# NT_MCUModule.net
KiCad netlist of a schematic drawn in EAGLE
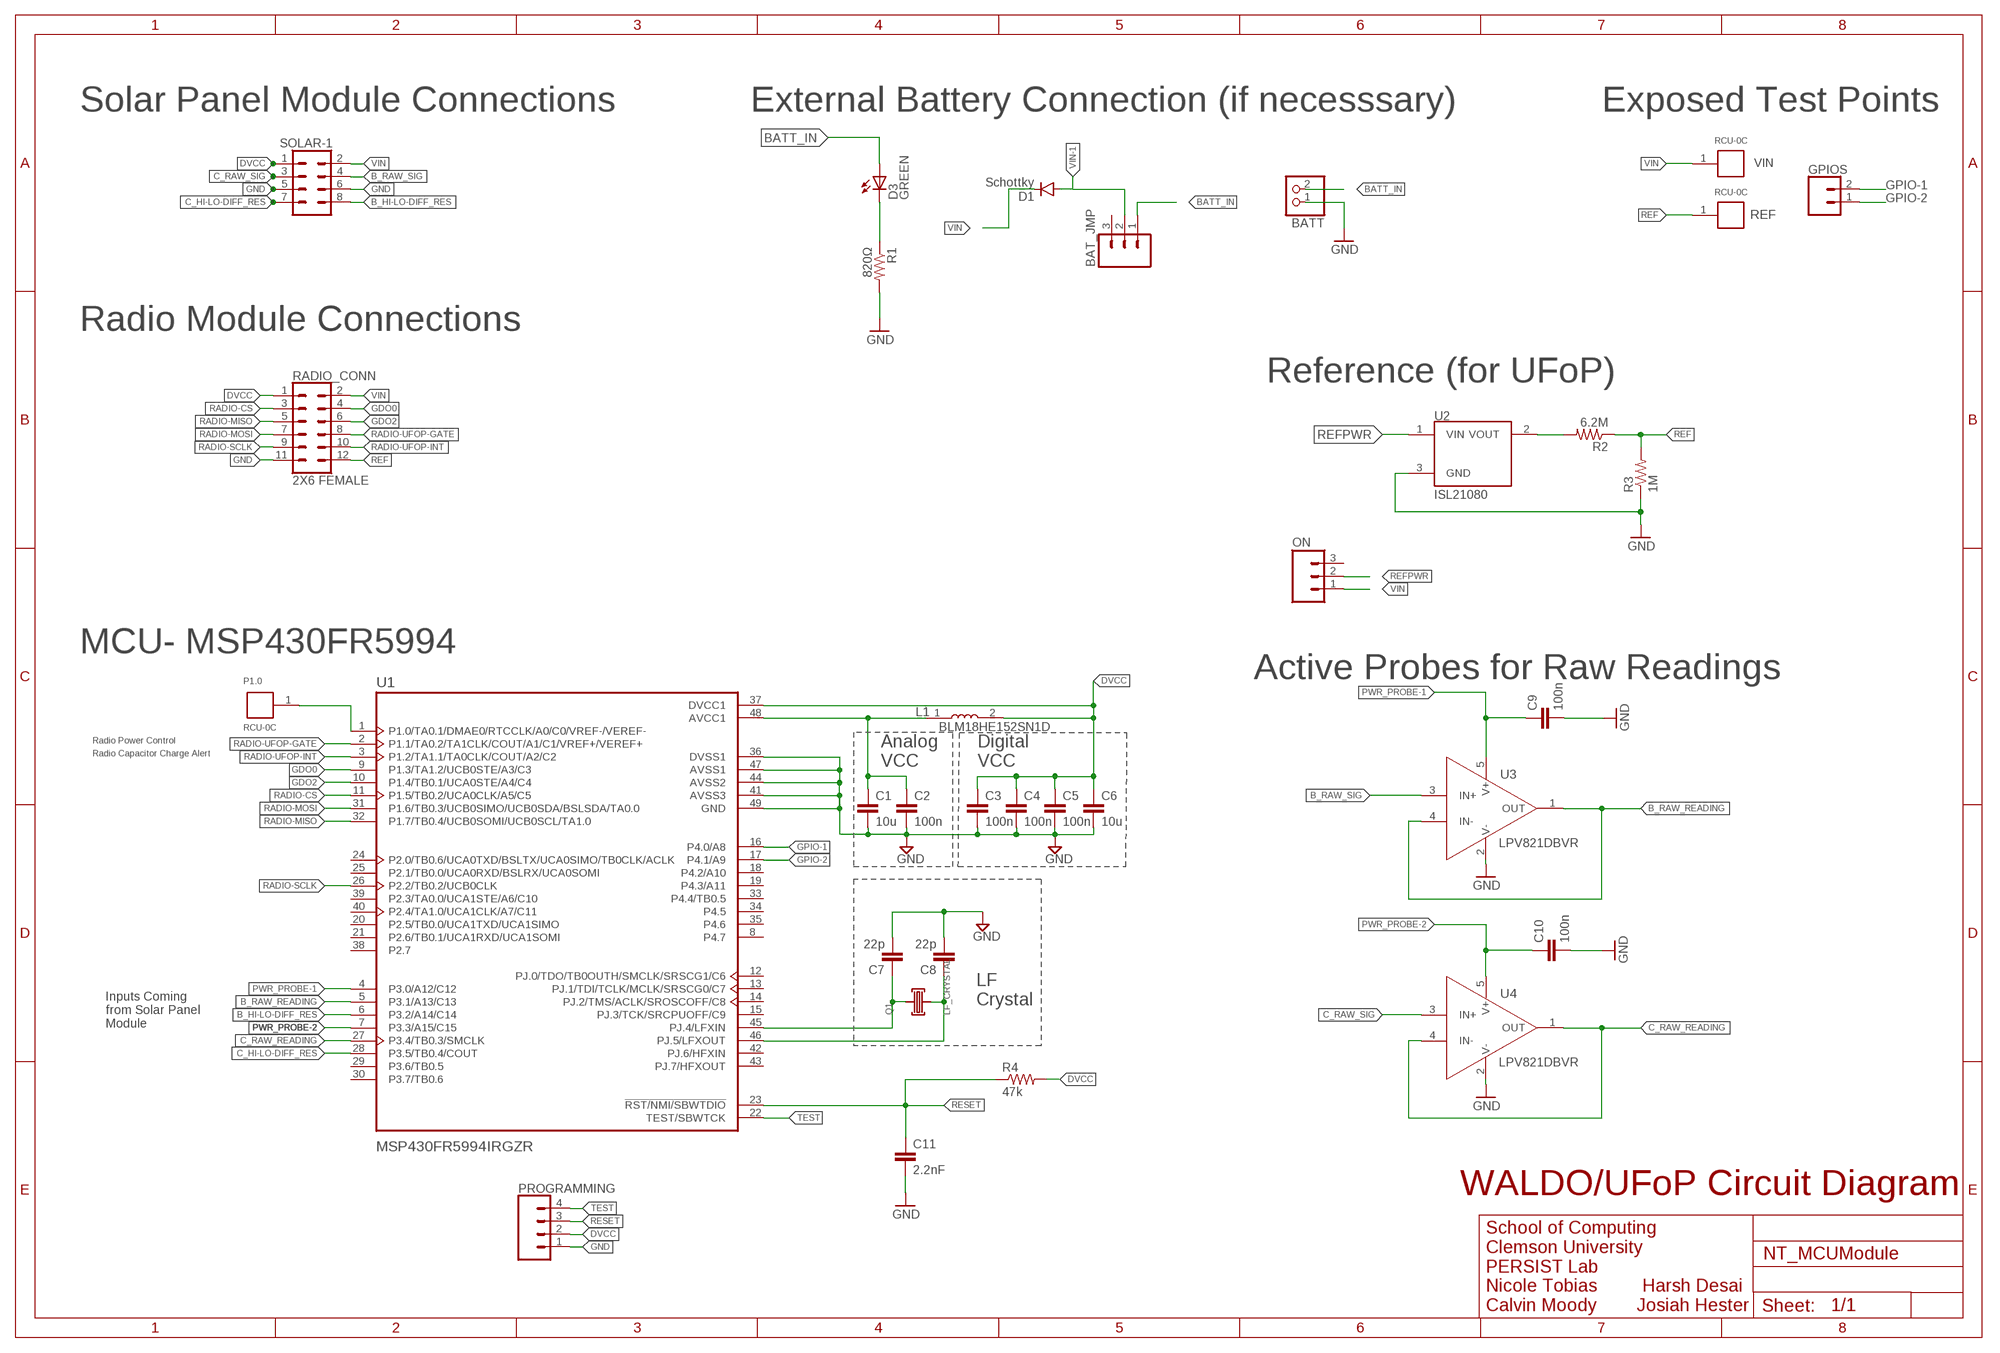
[diagram p0: schematic, sheet 1]

(export (version "E")
  (design (tool "Eeschema 10.0.6"))
  (components
    (comp (ref "BATT")
      (value "PINHD-1X2")
      (footprint "eagle-import:1X02")
      (libsource (lib "eagle-import") (part "PINHD-1X2"))
    )
    (comp (ref "BAT_JMP")
      (value "M03")
      (footprint "eagle-import:1X03-1.27MM")
      (libsource (lib "eagle-import") (part "M03"))
    )
    (comp (ref "C1")
      (value "10u")
      (footprint "eagle-import:C0603")
      (libsource (lib "eagle-import") (part "C-EUC0603"))
    )
    (comp (ref "C2")
      (value "100n")
      (footprint "eagle-import:C0603")
      (libsource (lib "eagle-import") (part "C-EUC0603"))
    )
    (comp (ref "C3")
      (value "100n")
      (footprint "eagle-import:C0603")
      (libsource (lib "eagle-import") (part "C-EUC0603"))
    )
    (comp (ref "C4")
      (value "100n")
      (footprint "eagle-import:C0603")
      (libsource (lib "eagle-import") (part "C-EUC0603"))
    )
    (comp (ref "C5")
      (value "100n")
      (footprint "eagle-import:C0603")
      (libsource (lib "eagle-import") (part "C-EUC0603"))
    )
    (comp (ref "C6")
      (value "10u")
      (footprint "eagle-import:C0603")
      (libsource (lib "eagle-import") (part "C-EUC0603"))
    )
    (comp (ref "C7")
      (value "22p")
      (footprint "eagle-import:C0603")
      (libsource (lib "eagle-import") (part "C-EUC0603"))
    )
    (comp (ref "C8")
      (value "22p")
      (footprint "eagle-import:C0603")
      (libsource (lib "eagle-import") (part "C-EUC0603"))
    )
    (comp (ref "C9")
      (value "100n")
      (footprint "eagle-import:C0603")
      (libsource (lib "eagle-import") (part "C-EUC0603"))
    )
    (comp (ref "C10")
      (value "100n")
      (footprint "eagle-import:C0603")
      (libsource (lib "eagle-import") (part "C-EUC0603"))
    )
    (comp (ref "C11")
      (value "2.2nF")
      (footprint "eagle-import:C0603")
      (libsource (lib "eagle-import") (part "C-EUC0603"))
    )
    (comp (ref "D1")
      (value "Schottky")
      (footprint "eagle-import:SOD523")
      (libsource (lib "eagle-import") (part "DIODESOD523"))
    )
    (comp (ref "D3")
      (value "GREEN")
      (footprint "eagle-import:CHIP-LED0805")
      (libsource (lib "eagle-import") (part "LEDCHIP-LED0805"))
    )
    (comp (ref "GPIOS")
      (value "CONN_02")
      (footprint "eagle-import:1X02")
      (libsource (lib "eagle-import") (part "CONN_02"))
    )
    (comp (ref "L1")
      (value "BLM18HE152SN1D")
      (footprint "eagle-import:INDC1608X95")
      (fields (field (name "DIGI-KEY_PART_NUMBER") "490-5216-1-ND") (field (name "MF") "Murata"))
      (libsource (lib "eagle-import") (part "BLM18HE152SN1D"))
    )
    (comp (ref "ON")
      (value "M03")
      (footprint "eagle-import:1X03-1.27MM")
      (libsource (lib "eagle-import") (part "M03"))
    )
    (comp (ref "P1.0")
      (value "RCU-0C")
      (footprint "eagle-import:TE_RCU-0C")
      (fields
        (field (name "COMMENT") "RCU-0C _1625854-3_")
        (field (name "MF") "TE Connectivity")
        (field (name "TOLERANCE") "0%")
      )
      (libsource (lib "eagle-import") (part "RCU-0C"))
    )
    (comp (ref "PROGRAMMING")
      (value "CONN_04")
      (footprint "eagle-import:1X04")
      (libsource (lib "eagle-import") (part "CONN_04"))
    )
    (comp (ref "Q1")
      (value "LF_CRYSTAL")
      (footprint "eagle-import:LF_CRYSTAL")
      (libsource (lib "eagle-import") (part "LF_CRYSTAL"))
    )
    (comp (ref "R1")
      (value "820Ω")
      (footprint "eagle-import:0603-RES")
      (libsource (lib "eagle-import") (part "RESISTOR0603"))
    )
    (comp (ref "R2")
      (value "6.2M")
      (footprint "eagle-import:0603-RES")
      (libsource (lib "eagle-import") (part "RESISTOR0603-RES"))
    )
    (comp (ref "R3")
      (value "1M")
      (footprint "eagle-import:0603-RES")
      (libsource (lib "eagle-import") (part "RESISTOR0603-RES"))
    )
    (comp (ref "R4")
      (value "47k")
      (footprint "eagle-import:0603-RES")
      (libsource (lib "eagle-import") (part "RESISTOR0603-RES"))
    )
    (comp (ref "RADIO_CONN")
      (value "2X6 FEMALE")
      (footprint "eagle-import:2X6")
      (libsource (lib "eagle-import") (part "CONN_06X2PTH_FEMALE"))
    )
    (comp (ref "REF")
      (value "RCU-0C")
      (footprint "eagle-import:TE_RCU-0C")
      (fields
        (field (name "COMMENT") "RCU-0C _1625854-3_")
        (field (name "MF") "TE Connectivity")
        (field (name "TOLERANCE") "0%")
      )
      (libsource (lib "eagle-import") (part "RCU-0C"))
    )
    (comp (ref "SOLAR-1")
      (value "CONN_04X2")
      (footprint "eagle-import:2X4")
      (libsource (lib "eagle-import") (part "CONN_04X2"))
    )
    (comp (ref "U1")
      (value "MSP430FR5994IRGZR")
      (footprint "eagle-import:QFN50P700X700X100-49N")
      (fields (field (name "MF") "Texas Instruments"))
      (libsource (lib "eagle-import") (part "MSP430FR5994IRGZR"))
    )
    (comp (ref "U2")
      (value "ISL21080")
      (footprint "eagle-import:SOT-23")
      (libsource (lib "eagle-import") (part "ISL21080"))
    )
    (comp (ref "U3")
      (value "LPV821DBVR")
      (footprint "eagle-import:SOT95P280X145-5N")
      (fields (field (name "DIGI-KEY_PART_NUMBER") "296-47911-1-ND") (field (name "MF") "Texas Instruments"))
      (libsource (lib "eagle-import") (part "LPV821DBVR"))
    )
    (comp (ref "U4")
      (value "LPV821DBVR")
      (footprint "eagle-import:SOT95P280X145-5N")
      (fields (field (name "DIGI-KEY_PART_NUMBER") "296-47911-1-ND") (field (name "MF") "Texas Instruments"))
      (libsource (lib "eagle-import") (part "LPV821DBVR"))
    )
    (comp (ref "VIN")
      (value "RCU-0C")
      (footprint "eagle-import:TE_RCU-0C")
      (fields
        (field (name "COMMENT") "RCU-0C _1625854-3_")
        (field (name "MF") "TE Connectivity")
        (field (name "TOLERANCE") "0%")
      )
      (libsource (lib "eagle-import") (part "RCU-0C"))
    )
  )
  (nets
    (net (code "1") (name "BATT_IN") (class "Default")
      (node (ref "BATT") (pin "2") (pinfunction "2_2") (pintype "passive"))
      (node (ref "BAT_JMP") (pin "1") (pinfunction "1_1") (pintype "passive"))
      (node (ref "D3") (pin "A") (pinfunction "A_A") (pintype "passive"))
    )
    (net (code "2") (name "B_HI-LO-DIFF_RES") (class "Default")
      (node (ref "SOLAR-1") (pin "8") (pinfunction "8_8") (pintype "passive"))
      (node (ref "U1") (pin "6") (pinfunction "P3.2/A14/C14_6") (pintype "bidirectional"))
    )
    (net (code "3") (name "B_RAW_READING") (class "Default")
      (node (ref "U1") (pin "5") (pinfunction "P3.1/A13/C13_5") (pintype "bidirectional"))
      (node (ref "U3") (pin "1") (pinfunction "OUT_1") (pintype "output"))
      (node (ref "U3") (pin "4") (pinfunction "IN-_4") (pintype "input"))
    )
    (net (code "4") (name "B_RAW_SIG") (class "Default")
      (node (ref "SOLAR-1") (pin "4") (pinfunction "4_4") (pintype "passive"))
      (node (ref "U3") (pin "3") (pinfunction "IN+_3") (pintype "input"))
    )
    (net (code "5") (name "C_HI-LO-DIFF_RES") (class "Default")
      (node (ref "SOLAR-1") (pin "7") (pinfunction "7_7") (pintype "passive"))
      (node (ref "U1") (pin "28") (pinfunction "P3.5/TB0.4/COUT_28") (pintype "bidirectional"))
    )
    (net (code "6") (name "C_RAW_READING") (class "Default")
      (node (ref "U1") (pin "27") (pinfunction "P3.4/TB0.3/SMCLK_27") (pintype "bidirectional"))
      (node (ref "U4") (pin "1") (pinfunction "OUT_1") (pintype "output"))
      (node (ref "U4") (pin "4") (pinfunction "IN-_4") (pintype "input"))
    )
    (net (code "7") (name "C_RAW_SIG") (class "Default")
      (node (ref "SOLAR-1") (pin "3") (pinfunction "3_3") (pintype "passive"))
      (node (ref "U4") (pin "3") (pinfunction "IN+_3") (pintype "input"))
    )
    (net (code "8") (name "DVCC") (class "Default")
      (node (ref "C3") (pin "1") (pinfunction "1_1") (pintype "passive"))
      (node (ref "C4") (pin "1") (pinfunction "1_1") (pintype "passive"))
      (node (ref "C5") (pin "1") (pinfunction "1_1") (pintype "passive"))
      (node (ref "C6") (pin "1") (pinfunction "1_1") (pintype "passive"))
      (node (ref "L1") (pin "2") (pinfunction "2_2") (pintype "passive"))
      (node (ref "PROGRAMMING") (pin "2") (pinfunction "2_2") (pintype "passive"))
      (node (ref "R4") (pin "2") (pinfunction "2_2") (pintype "passive"))
      (node (ref "RADIO_CONN") (pin "1") (pinfunction "1_1") (pintype "passive"))
      (node (ref "SOLAR-1") (pin "1") (pinfunction "1_1") (pintype "passive"))
      (node (ref "U1") (pin "37") (pinfunction "DVCC1_37") (pintype "power_in"))
    )
    (net (code "9") (name "GDO0") (class "Default")
      (node (ref "RADIO_CONN") (pin "4") (pinfunction "4_4") (pintype "passive"))
      (node (ref "U1") (pin "9") (pinfunction "P1.3/TA1.2/UCB0STE/A3/C3_9") (pintype "bidirectional"))
    )
    (net (code "10") (name "GDO2") (class "Default")
      (node (ref "RADIO_CONN") (pin "6") (pinfunction "6_6") (pintype "passive"))
      (node (ref "U1") (pin "10") (pinfunction "P1.4/TB0.1/UCA0STE/A4/C4_10") (pintype "bidirectional"))
    )
    (net (code "11") (name "GND") (class "Default")
      (node (ref "BATT") (pin "1") (pinfunction "1_1") (pintype "passive"))
      (node (ref "C1") (pin "2") (pinfunction "2_2") (pintype "passive"))
      (node (ref "C10") (pin "2") (pinfunction "2_2") (pintype "passive"))
      (node (ref "C11") (pin "2") (pinfunction "2_2") (pintype "passive"))
      (node (ref "C2") (pin "2") (pinfunction "2_2") (pintype "passive"))
      (node (ref "C3") (pin "2") (pinfunction "2_2") (pintype "passive"))
      (node (ref "C4") (pin "2") (pinfunction "2_2") (pintype "passive"))
      (node (ref "C5") (pin "2") (pinfunction "2_2") (pintype "passive"))
      (node (ref "C6") (pin "2") (pinfunction "2_2") (pintype "passive"))
      (node (ref "C7") (pin "2") (pinfunction "2_2") (pintype "passive"))
      (node (ref "C8") (pin "2") (pinfunction "2_2") (pintype "passive"))
      (node (ref "C9") (pin "2") (pinfunction "2_2") (pintype "passive"))
      (node (ref "PROGRAMMING") (pin "1") (pinfunction "1_1") (pintype "passive"))
      (node (ref "R1") (pin "2") (pinfunction "2_2") (pintype "passive"))
      (node (ref "R3") (pin "1") (pinfunction "1_1") (pintype "passive"))
      (node (ref "RADIO_CONN") (pin "11") (pinfunction "11_11") (pintype "passive"))
      (node (ref "SOLAR-1") (pin "5") (pinfunction "5_5") (pintype "passive"))
      (node (ref "SOLAR-1") (pin "6") (pinfunction "6_6") (pintype "passive"))
      (node (ref "U1") (pin "36") (pinfunction "DVSS1_36") (pintype "power_in"))
      (node (ref "U1") (pin "41") (pinfunction "AVSS3_41") (pintype "power_in"))
      (node (ref "U1") (pin "44") (pinfunction "AVSS2_44") (pintype "power_in"))
      (node (ref "U1") (pin "47") (pinfunction "AVSS1_47") (pintype "power_in"))
      (node (ref "U1") (pin "49") (pinfunction "GND_49") (pintype "power_in"))
      (node (ref "U2") (pin "3") (pinfunction "GND_3") (pintype "bidirectional"))
      (node (ref "U3") (pin "2") (pinfunction "V-_2") (pintype "power_in"))
      (node (ref "U4") (pin "2") (pinfunction "V-_2") (pintype "power_in"))
    )
    (net (code "12") (name "GPIO-1") (class "Default")
      (node (ref "GPIOS") (pin "2") (pinfunction "2_2") (pintype "passive"))
      (node (ref "U1") (pin "16") (pinfunction "P4.0/A8_16") (pintype "bidirectional"))
    )
    (net (code "13") (name "GPIO-2") (class "Default")
      (node (ref "GPIOS") (pin "1") (pinfunction "1_1") (pintype "passive"))
      (node (ref "U1") (pin "17") (pinfunction "P4.1/A9_17") (pintype "bidirectional"))
    )
    (net (code "14") (name "Net-(D3-PadC)") (class "Default")
      (node (ref "D3") (pin "C") (pinfunction "C_C") (pintype "passive"))
      (node (ref "R1") (pin "1") (pinfunction "1_1") (pintype "passive"))
    )
    (net (code "15") (name "Net-(U1-AVCC1)") (class "Default")
      (node (ref "C1") (pin "1") (pinfunction "1_1") (pintype "passive"))
      (node (ref "C2") (pin "1") (pinfunction "1_1") (pintype "passive"))
      (node (ref "L1") (pin "1") (pinfunction "1_1") (pintype "passive"))
      (node (ref "U1") (pin "48") (pinfunction "AVCC1_48") (pintype "power_in"))
    )
    (net (code "16") (name "Net-(U1-P1.0{slash}TA0.1{slash}DMAE0{slash}RTCCLK{slash}A0{slash}C0{slash}VREF-{slash}VEREF-)") (class "Default")
      (node (ref "P1.0") (pin "1") (pinfunction "1_1") (pintype "passive"))
      (node (ref "U1") (pin "1") (pinfunction "P1.0/TA0.1/DMAE0/RTCCLK/A0/C0/VREF-/VEREF-_1") (pintype "bidirectional"))
    )
    (net (code "17") (name "Net-(U1-PJ.4{slash}LFXIN)") (class "Default")
      (node (ref "C7") (pin "1") (pinfunction "1_1") (pintype "passive"))
      (node (ref "Q1") (pin "1") (pinfunction "1_1") (pintype "bidirectional"))
      (node (ref "U1") (pin "45") (pinfunction "PJ.4/LFXIN_45") (pintype "bidirectional"))
    )
    (net (code "18") (name "Net-(U1-PJ.5{slash}LFXOUT)") (class "Default")
      (node (ref "C8") (pin "1") (pinfunction "1_1") (pintype "passive"))
      (node (ref "Q1") (pin "2") (pinfunction "2_2") (pintype "bidirectional"))
      (node (ref "U1") (pin "46") (pinfunction "PJ.5/LFXOUT_46") (pintype "bidirectional"))
    )
    (net (code "19") (name "Net-(U2-VOUT)") (class "Default")
      (node (ref "R2") (pin "2") (pinfunction "2_2") (pintype "passive"))
      (node (ref "U2") (pin "2") (pinfunction "VOUT_2") (pintype "bidirectional"))
    )
    (net (code "20") (name "PWR_PROBE-1") (class "Default")
      (node (ref "C9") (pin "1") (pinfunction "1_1") (pintype "passive"))
      (node (ref "U1") (pin "4") (pinfunction "P3.0/A12/C12_4") (pintype "bidirectional"))
      (node (ref "U3") (pin "5") (pinfunction "V+_5") (pintype "power_in"))
    )
    (net (code "21") (name "PWR_PROBE-2") (class "Default")
      (node (ref "C10") (pin "1") (pinfunction "1_1") (pintype "passive"))
      (node (ref "U1") (pin "7") (pinfunction "P3.3/A15/C15_7") (pintype "bidirectional"))
      (node (ref "U4") (pin "5") (pinfunction "V+_5") (pintype "power_in"))
    )
    (net (code "22") (name "RADIO-CS") (class "Default")
      (node (ref "RADIO_CONN") (pin "3") (pinfunction "3_3") (pintype "passive"))
      (node (ref "U1") (pin "11") (pinfunction "P1.5/TB0.2/UCA0CLK/A5/C5_11") (pintype "bidirectional"))
    )
    (net (code "23") (name "RADIO-MISO") (class "Default")
      (node (ref "RADIO_CONN") (pin "5") (pinfunction "5_5") (pintype "passive"))
      (node (ref "U1") (pin "32") (pinfunction "P1.7/TB0.4/UCB0SOMI/UCB0SCL/TA1.0_32") (pintype "bidirectional"))
    )
    (net (code "24") (name "RADIO-MOSI") (class "Default")
      (node (ref "RADIO_CONN") (pin "7") (pinfunction "7_7") (pintype "passive"))
      (node (ref "U1") (pin "31") (pinfunction "P1.6/TB0.3/UCB0SIMO/UCB0SDA/BSLSDA/TA0.0_31") (pintype "bidirectional"))
    )
    (net (code "25") (name "RADIO-SCLK") (class "Default")
      (node (ref "RADIO_CONN") (pin "9") (pinfunction "9_9") (pintype "passive"))
      (node (ref "U1") (pin "26") (pinfunction "P2.2/TB0.2/UCB0CLK_26") (pintype "bidirectional"))
    )
    (net (code "26") (name "RADIO-UFOP-GATE") (class "Default")
      (node (ref "RADIO_CONN") (pin "8") (pinfunction "8_8") (pintype "passive"))
      (node (ref "U1") (pin "2") (pinfunction "P1.1/TA0.2/TA1CLK/COUT/A1/C1/VREF+/VEREF+_2") (pintype "bidirectional"))
    )
    (net (code "27") (name "RADIO-UFOP-INT") (class "Default")
      (node (ref "RADIO_CONN") (pin "10") (pinfunction "10_10") (pintype "passive"))
      (node (ref "U1") (pin "3") (pinfunction "P1.2/TA1.1/TA0CLK/COUT/A2/C2_3") (pintype "bidirectional"))
    )
    (net (code "28") (name "REF") (class "Default")
      (node (ref "R2") (pin "1") (pinfunction "1_1") (pintype "passive"))
      (node (ref "R3") (pin "2") (pinfunction "2_2") (pintype "passive"))
      (node (ref "RADIO_CONN") (pin "12") (pinfunction "12_12") (pintype "passive"))
      (node (ref "REF") (pin "1") (pinfunction "1_1") (pintype "passive"))
    )
    (net (code "29") (name "REFPWR") (class "Default")
      (node (ref "ON") (pin "2") (pinfunction "2_2") (pintype "passive"))
      (node (ref "U2") (pin "1") (pinfunction "VIN_1") (pintype "bidirectional"))
    )
    (net (code "30") (name "RESET") (class "Default")
      (node (ref "C11") (pin "1") (pinfunction "1_1") (pintype "passive"))
      (node (ref "PROGRAMMING") (pin "3") (pinfunction "3_3") (pintype "passive"))
      (node (ref "R4") (pin "1") (pinfunction "1_1") (pintype "passive"))
      (node (ref "U1") (pin "23") (pinfunction "~{RST/NMI/SBWTDIO}_23") (pintype "bidirectional"))
    )
    (net (code "31") (name "TEST") (class "Default")
      (node (ref "PROGRAMMING") (pin "4") (pinfunction "4_4") (pintype "passive"))
      (node (ref "U1") (pin "22") (pinfunction "TEST/SBWTCK_22") (pintype "bidirectional"))
    )
    (net (code "32") (name "VIN") (class "Default")
      (node (ref "D1") (pin "C") (pinfunction "C_C") (pintype "passive"))
      (node (ref "ON") (pin "1") (pinfunction "1_1") (pintype "passive"))
      (node (ref "RADIO_CONN") (pin "2") (pinfunction "2_2") (pintype "passive"))
      (node (ref "SOLAR-1") (pin "2") (pinfunction "2_2") (pintype "passive"))
      (node (ref "VIN") (pin "1") (pinfunction "1_1") (pintype "passive"))
    )
    (net (code "33") (name "VIN-1") (class "Default")
      (node (ref "BAT_JMP") (pin "2") (pinfunction "2_2") (pintype "passive"))
      (node (ref "D1") (pin "A") (pinfunction "A_A") (pintype "passive"))
    )
    (net (code "34") (name "unconnected-(BAT_JMP-Pad3)") (class "Default")
      (node (ref "BAT_JMP") (pin "3") (pinfunction "3_3") (pintype "passive"))
    )
    (net (code "35") (name "unconnected-(ON-Pad3)") (class "Default")
      (node (ref "ON") (pin "3") (pinfunction "3_3") (pintype "passive"))
    )
    (net (code "36") (name "unconnected-(U1-P2.0{slash}TB0.6{slash}UCA0TXD{slash}BSLTX{slash}UCA0SIMO{slash}TB0CLK{slash}ACLK-Pad24)") (class "Default")
      (node (ref "U1") (pin "24") (pinfunction "P2.0/TB0.6/UCA0TXD/BSLTX/UCA0SIMO/TB0CLK/ACLK_24") (pintype "bidirectional"))
    )
    (net (code "37") (name "unconnected-(U1-P2.1{slash}TB0.0{slash}UCA0RXD{slash}BSLRX{slash}UCA0SOMI-Pad25)") (class "Default")
      (node (ref "U1") (pin "25") (pinfunction "P2.1/TB0.0/UCA0RXD/BSLRX/UCA0SOMI_25") (pintype "bidirectional"))
    )
    (net (code "38") (name "unconnected-(U1-P2.3{slash}TA0.0{slash}UCA1STE{slash}A6{slash}C10-Pad39)") (class "Default")
      (node (ref "U1") (pin "39") (pinfunction "P2.3/TA0.0/UCA1STE/A6/C10_39") (pintype "bidirectional"))
    )
    (net (code "39") (name "unconnected-(U1-P2.4{slash}TA1.0{slash}UCA1CLK{slash}A7{slash}C11-Pad40)") (class "Default")
      (node (ref "U1") (pin "40") (pinfunction "P2.4/TA1.0/UCA1CLK/A7/C11_40") (pintype "bidirectional"))
    )
    (net (code "40") (name "unconnected-(U1-P2.5{slash}TB0.0{slash}UCA1TXD{slash}UCA1SIMO-Pad20)") (class "Default")
      (node (ref "U1") (pin "20") (pinfunction "P2.5/TB0.0/UCA1TXD/UCA1SIMO_20") (pintype "bidirectional"))
    )
    (net (code "41") (name "unconnected-(U1-P2.6{slash}TB0.1{slash}UCA1RXD{slash}UCA1SOMI-Pad21)") (class "Default")
      (node (ref "U1") (pin "21") (pinfunction "P2.6/TB0.1/UCA1RXD/UCA1SOMI_21") (pintype "bidirectional"))
    )
    (net (code "42") (name "unconnected-(U1-P2.7-Pad38)") (class "Default")
      (node (ref "U1") (pin "38") (pinfunction "P2.7_38") (pintype "bidirectional"))
    )
    (net (code "43") (name "unconnected-(U1-P3.6{slash}TB0.5-Pad29)") (class "Default")
      (node (ref "U1") (pin "29") (pinfunction "P3.6/TB0.5_29") (pintype "bidirectional"))
    )
    (net (code "44") (name "unconnected-(U1-P3.7{slash}TB0.6-Pad30)") (class "Default")
      (node (ref "U1") (pin "30") (pinfunction "P3.7/TB0.6_30") (pintype "bidirectional"))
    )
    (net (code "45") (name "unconnected-(U1-P4.2{slash}A10-Pad18)") (class "Default")
      (node (ref "U1") (pin "18") (pinfunction "P4.2/A10_18") (pintype "bidirectional"))
    )
    (net (code "46") (name "unconnected-(U1-P4.3{slash}A11-Pad19)") (class "Default")
      (node (ref "U1") (pin "19") (pinfunction "P4.3/A11_19") (pintype "bidirectional"))
    )
    (net (code "47") (name "unconnected-(U1-P4.4{slash}TB0.5-Pad33)") (class "Default")
      (node (ref "U1") (pin "33") (pinfunction "P4.4/TB0.5_33") (pintype "bidirectional"))
    )
    (net (code "48") (name "unconnected-(U1-P4.5-Pad34)") (class "Default")
      (node (ref "U1") (pin "34") (pinfunction "P4.5_34") (pintype "bidirectional"))
    )
    (net (code "49") (name "unconnected-(U1-P4.6-Pad35)") (class "Default")
      (node (ref "U1") (pin "35") (pinfunction "P4.6_35") (pintype "bidirectional"))
    )
    (net (code "50") (name "unconnected-(U1-P4.7-Pad8)") (class "Default")
      (node (ref "U1") (pin "8") (pinfunction "P4.7_8") (pintype "bidirectional"))
    )
    (net (code "51") (name "unconnected-(U1-PJ.0{slash}TDO{slash}TB0OUTH{slash}SMCLK{slash}SRSCG1{slash}C6-Pad12)") (class "Default")
      (node (ref "U1") (pin "12") (pinfunction "PJ.0/TDO/TB0OUTH/SMCLK/SRSCG1/C6_12") (pintype "bidirectional"))
    )
    (net (code "52") (name "unconnected-(U1-PJ.1{slash}TDI{slash}TCLK{slash}MCLK{slash}SRSCG0{slash}C7-Pad13)") (class "Default")
      (node (ref "U1") (pin "13") (pinfunction "PJ.1/TDI/TCLK/MCLK/SRSCG0/C7_13") (pintype "bidirectional"))
    )
    (net (code "53") (name "unconnected-(U1-PJ.2{slash}TMS{slash}ACLK{slash}SROSCOFF{slash}C8-Pad14)") (class "Default")
      (node (ref "U1") (pin "14") (pinfunction "PJ.2/TMS/ACLK/SROSCOFF/C8_14") (pintype "bidirectional"))
    )
    (net (code "54") (name "unconnected-(U1-PJ.3{slash}TCK{slash}SRCPUOFF{slash}C9-Pad15)") (class "Default")
      (node (ref "U1") (pin "15") (pinfunction "PJ.3/TCK/SRCPUOFF/C9_15") (pintype "bidirectional"))
    )
    (net (code "55") (name "unconnected-(U1-PJ.6{slash}HFXIN-Pad42)") (class "Default")
      (node (ref "U1") (pin "42") (pinfunction "PJ.6/HFXIN_42") (pintype "bidirectional"))
    )
    (net (code "56") (name "unconnected-(U1-PJ.7{slash}HFXOUT-Pad43)") (class "Default")
      (node (ref "U1") (pin "43") (pinfunction "PJ.7/HFXOUT_43") (pintype "bidirectional"))
    )
  )
)
